# MCU.net
KiCad netlist of a schematic drawn in Altium Designer
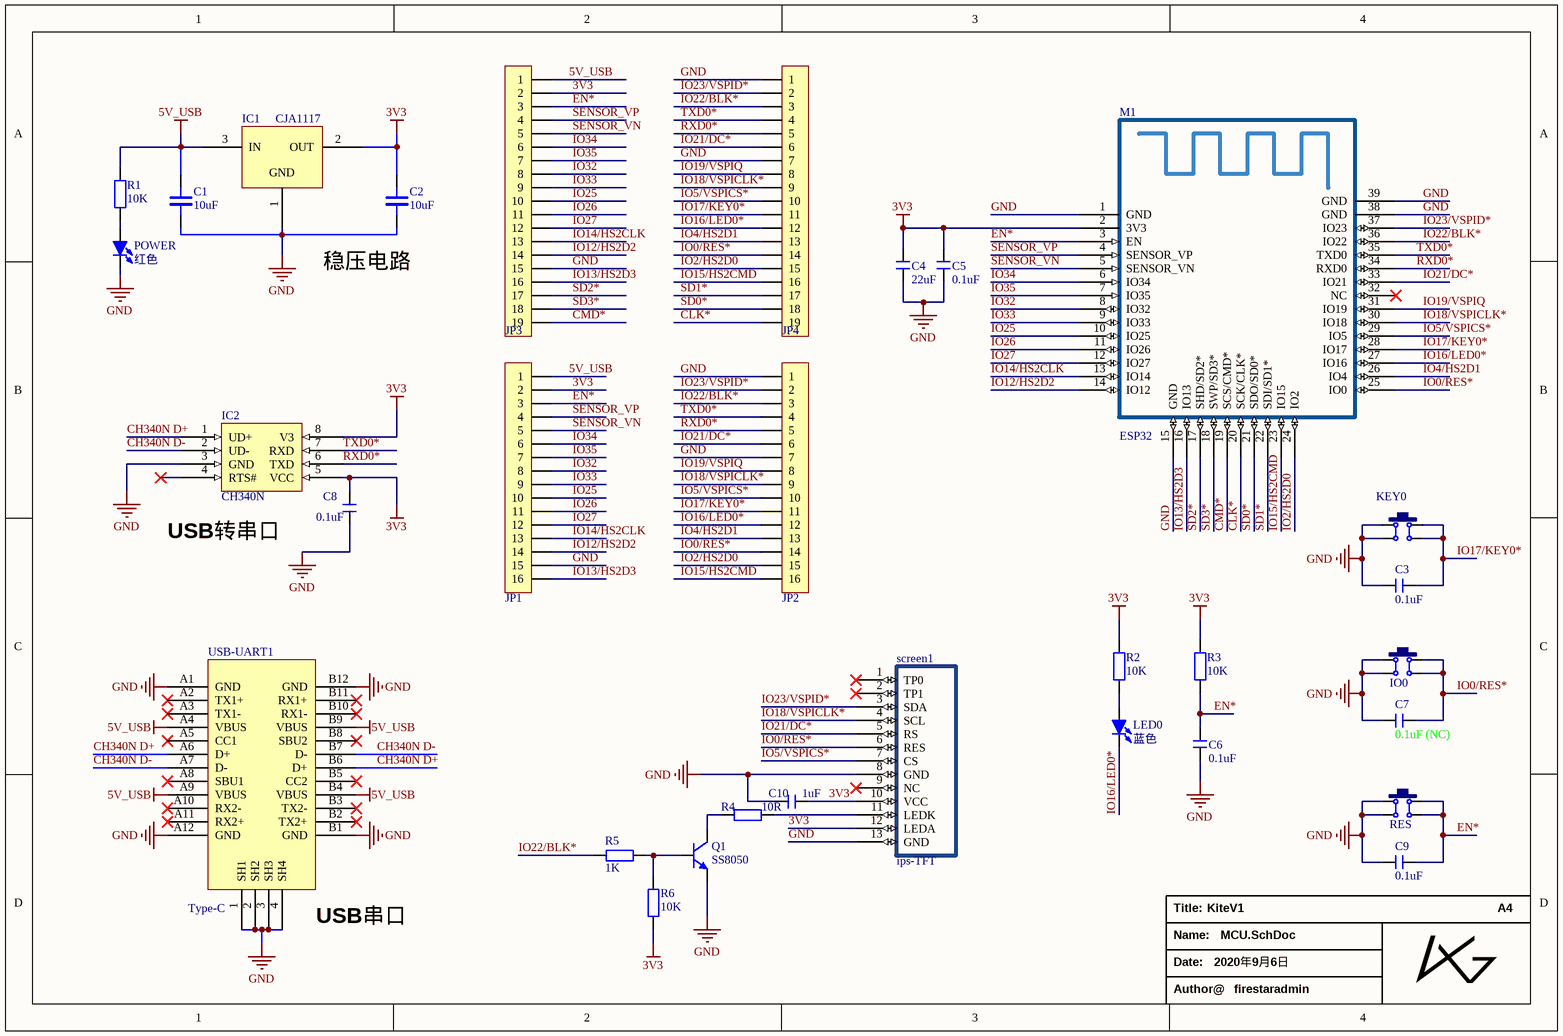
[diagram p0: MCU.SchDoc]

(export (version "E")
  (design (tool "Eeschema 10.0.6"))
  (components
    (comp (ref "C1")
      (value "10uF")
      (footprint "C 0805_L")
      (description "Capacitor")
      (libsource (lib "General") (part "CAP"))
    )
    (comp (ref "C2")
      (value "10uF")
      (footprint "C 0805_L")
      (description "Capacitor")
      (libsource (lib "General") (part "CAP"))
    )
    (comp (ref "C3")
      (value "0.1uF")
      (footprint "C 0603_M")
      (description "无极性贴片电容")
      (fields (field (name "版权归属") "源创客"))
      (libsource (lib "SCH-电阻-电容-电感") (part "C"))
    )
    (comp (ref "C4")
      (value "22uF")
      (footprint "C 0603_M")
      (description "无极性贴片电容")
      (fields (field (name "版权归属") "源创客"))
      (libsource (lib "SCH-电阻-电容-电感") (part "C"))
    )
    (comp (ref "C5")
      (value "0.1uF")
      (footprint "C 0603_M")
      (description "无极性贴片电容")
      (fields (field (name "版权归属") "源创客"))
      (libsource (lib "SCH-电阻-电容-电感") (part "C"))
    )
    (comp (ref "C6")
      (value "0.1uF")
      (footprint "C 0603_M")
      (description "无极性贴片电容")
      (fields (field (name "版权归属") "源创客"))
      (libsource (lib "SCH-电阻-电容-电感") (part "C"))
    )
    (comp (ref "C7")
      (value "0.1uF (NC)")
      (footprint "C 0603_M")
      (description "无极性贴片电容")
      (fields (field (name "版权归属") "源创客"))
      (libsource (lib "SCH-电阻-电容-电感") (part "C"))
    )
    (comp (ref "C8")
      (value "0.1uF")
      (footprint "C 0603_M")
      (description "无极性贴片电容")
      (fields (field (name "版权归属") "源创客"))
      (libsource (lib "altium-import") (part "root_1_C_"))
    )
    (comp (ref "C9")
      (value "0.1uF")
      (footprint "C 0603_M")
      (description "无极性贴片电容")
      (fields (field (name "版权归属") "源创客"))
      (libsource (lib "SCH-电阻-电容-电感") (part "C"))
    )
    (comp (ref "C10")
      (value "1uF")
      (footprint "C 0603_M")
      (description "无极性贴片电容")
      (fields (field (name "版权归属") "源创客"))
      (libsource (lib "SCH-电阻-电容-电感") (part "C"))
    )
    (comp (ref "IC1")
      (value "CJA1117")
      (footprint "SOT89_M")
      (libsource (lib "altium-import") (part "root_0_CJA1117_"))
    )
    (comp (ref "IC2")
      (value "CH340N")
      (footprint "SOP8_M")
      (description "USB 转串口芯片 CH330/CH340N")
      (libsource (lib "altium-import") (part "root_0_CH340N_"))
    )
    (comp (ref "IO0")
      (value "key")
      (footprint "TSMD-3*4*2.5")
      (description "TS-3x4x2.5mm-4pin 轻触按键")
      (libsource (lib "SCH-按键-开关") (part "TS-3x4x2.5mm-4pin"))
    )
    (comp (ref "JP1")
      (value "HDR-1X16")
      (footprint "HDR2.54-LI-16P")
      (description "16P接插件")
      (fields (field (name "版权归属") "源创客"))
      (libsource (lib "SCH-接插件-脚距2.54") (part "Header 16"))
    )
    (comp (ref "JP2")
      (value "HDR-1X16")
      (footprint "HDR2.54-LI-16P")
      (description "16P接插件")
      (fields (field (name "版权归属") "源创客"))
      (libsource (lib "") (part "Header 16_1"))
    )
    (comp (ref "JP3")
      (value "HDR-1X19")
      (footprint "HDR2.54-LI-19P")
      (description "19P接插件")
      (fields (field (name "版权归属") "源创客"))
      (libsource (lib "") (part "Header 19_1"))
    )
    (comp (ref "JP4")
      (value "HDR-1X19")
      (footprint "HDR2.54-LI-19P")
      (description "19P接插件")
      (fields (field (name "版权归属") "源创客"))
      (libsource (lib "SCH-接插件-脚距2.54") (part "Header 19"))
    )
    (comp (ref "KEY0")
      (value "key")
      (footprint "TSMD-3*4*2.5")
      (description "TS-3x4x2.5mm-4pin 轻触按键")
      (libsource (lib "SCH-按键-开关") (part "TS-3x4x2.5mm-4pin"))
    )
    (comp (ref "LED0")
      (value "蓝色")
      (footprint "LED 0603R")
      (description "贴片LED")
      (fields (field (name "版权归属") "源创客"))
      (libsource (lib "SCH-LED") (part "LED-SMD"))
    )
    (comp (ref "M1")
      (value "ESP32")
      (footprint "ESP32-WROOM-32")
      (description "ESP32-WROOM-32 WIFI 蓝牙模组")
      (libsource (lib "SCH- 模块") (part "ESP32-WROOM-32"))
    )
    (comp (ref "POWER")
      (value "红色")
      (footprint "LED 0603R")
      (description "贴片LED")
      (fields (field (name "版权归属") "源创客"))
      (libsource (lib "SCH-LED") (part "LED-SMD"))
    )
    (comp (ref "Q1")
      (value "SS8050")
      (footprint "SOT23-3N")
      (description "高频放大-NPN型")
      (fields (field (name "版权归属") "源创客"))
      (libsource (lib "SCH-三极管") (part "8050-SMD"))
    )
    (comp (ref "R1")
      (value "10K")
      (footprint "R 0603_M")
      (description "贴片电阻")
      (fields (field (name "版权归属") "源创客"))
      (libsource (lib "SCH-电阻-电容-电感") (part "R"))
    )
    (comp (ref "R2")
      (value "10K")
      (footprint "R 0603_M")
      (description "贴片电阻")
      (fields (field (name "版权归属") "源创客"))
      (libsource (lib "SCH-电阻-电容-电感") (part "R"))
    )
    (comp (ref "R3")
      (value "10K")
      (footprint "R 0603_M")
      (description "贴片电阻")
      (fields (field (name "版权归属") "源创客"))
      (libsource (lib "SCH-电阻-电容-电感") (part "R"))
    )
    (comp (ref "R4")
      (value "10R")
      (footprint "R 0603_M")
      (description "贴片电阻")
      (fields (field (name "版权归属") "源创客"))
      (libsource (lib "SCH-电阻-电容-电感") (part "R"))
    )
    (comp (ref "R5")
      (value "1K")
      (footprint "R 0603_M")
      (description "贴片电阻")
      (fields (field (name "版权归属") "源创客"))
      (libsource (lib "SCH-电阻-电容-电感") (part "R"))
    )
    (comp (ref "R6")
      (value "10K")
      (footprint "R 0603_M")
      (description "贴片电阻")
      (fields (field (name "版权归属") "源创客"))
      (libsource (lib "SCH-电阻-电容-电感") (part "R"))
    )
    (comp (ref "RES")
      (value "key")
      (footprint "TSMD-3*4*2.5")
      (description "TS-3x4x2.5mm-4pin 轻触按键")
      (libsource (lib "SCH-按键-开关") (part "TS-3x4x2.5mm-4pin"))
    )
    (comp (ref "screen1")
      (value "ips-TFT")
      (footprint "ips-TFT-0.96寸-st7735-SPI")
      (description "中景园ips 0.96寸TFT显示屏ips液晶屏0.96寸st7735 ips显示屏 13pins")
      (libsource (lib "SCH-显示器件") (part "ips-TFT-0.96寸-st7735-SPI"))
    )
    (comp (ref "USB-UART1")
      (value "Type-C")
      (footprint "Type-C")
      (libsource (lib "altium-import") (part "root_0_Type-C_"))
    )
  )
  (nets
    (net (code "1") (name "/CH340N D+") (class "Default")
      (node (ref "IC2") (pin "1") (pinfunction "UD+_1") (pintype "input"))
      (node (ref "USB-UART1") (pin "A6") (pinfunction "D+_A6") (pintype "passive"))
      (node (ref "USB-UART1") (pin "B6") (pinfunction "D+_B6") (pintype "passive"))
    )
    (net (code "2") (name "/CH340N D-") (class "Default")
      (node (ref "IC2") (pin "2") (pinfunction "UD-_2") (pintype "input"))
      (node (ref "USB-UART1") (pin "A7") (pinfunction "D-_A7") (pintype "passive"))
      (node (ref "USB-UART1") (pin "B7") (pinfunction "D-_B7") (pintype "passive"))
    )
    (net (code "3") (name "/CLK*") (class "Default")
      (node (ref "JP4") (pin "19") (pinfunction "19_19") (pintype "passive"))
      (node (ref "M1") (pin "20") (pinfunction "SCK/CLK*_20") (pintype "bidirectional"))
    )
    (net (code "4") (name "/CMD*") (class "Default")
      (node (ref "JP3") (pin "19") (pinfunction "19_19") (pintype "passive"))
      (node (ref "M1") (pin "19") (pinfunction "SCS/CMD*_19") (pintype "bidirectional"))
    )
    (net (code "5") (name "/EN*") (class "Default")
      (node (ref "C6") (pin "1") (pinfunction "1_1") (pintype "passive"))
      (node (ref "C9") (pin "2") (pinfunction "2_2") (pintype "passive"))
      (node (ref "JP1") (pin "3") (pinfunction "3_3") (pintype "passive"))
      (node (ref "JP3") (pin "3") (pinfunction "3_3") (pintype "passive"))
      (node (ref "M1") (pin "3") (pinfunction "EN_3") (pintype "input"))
      (node (ref "R3") (pin "1") (pinfunction "1_1") (pintype "passive"))
      (node (ref "RES") (pin "3") (pinfunction "3_3") (pintype "passive"))
      (node (ref "RES") (pin "4") (pinfunction "4_4") (pintype "passive"))
    )
    (net (code "6") (name "/IO0{slash}RES*") (class "Default")
      (node (ref "C7") (pin "2") (pinfunction "2_2") (pintype "passive"))
      (node (ref "IO0") (pin "3") (pinfunction "3_3") (pintype "passive"))
      (node (ref "IO0") (pin "4") (pinfunction "4_4") (pintype "passive"))
      (node (ref "JP2") (pin "14") (pinfunction "14_14") (pintype "passive"))
      (node (ref "JP4") (pin "14") (pinfunction "14_14") (pintype "passive"))
      (node (ref "M1") (pin "25") (pinfunction "IO0_25") (pintype "bidirectional"))
      (node (ref "screen1") (pin "6") (pinfunction "RES_6") (pintype "bidirectional"))
    )
    (net (code "7") (name "/IO2{slash}HS2D0") (class "Default")
      (node (ref "JP2") (pin "15") (pinfunction "15_15") (pintype "passive"))
      (node (ref "JP4") (pin "15") (pinfunction "15_15") (pintype "passive"))
      (node (ref "M1") (pin "24") (pinfunction "IO2_24") (pintype "bidirectional"))
    )
    (net (code "8") (name "/IO4{slash}HS2D1") (class "Default")
      (node (ref "JP2") (pin "13") (pinfunction "13_13") (pintype "passive"))
      (node (ref "JP4") (pin "13") (pinfunction "13_13") (pintype "passive"))
      (node (ref "M1") (pin "26") (pinfunction "IO4_26") (pintype "bidirectional"))
    )
    (net (code "9") (name "/IO5{slash}VSPICS*") (class "Default")
      (node (ref "JP2") (pin "10") (pinfunction "10_10") (pintype "passive"))
      (node (ref "JP4") (pin "10") (pinfunction "10_10") (pintype "passive"))
      (node (ref "M1") (pin "29") (pinfunction "IO5_29") (pintype "bidirectional"))
      (node (ref "screen1") (pin "7") (pinfunction "CS_7") (pintype "bidirectional"))
    )
    (net (code "10") (name "/IO12{slash}HS2D2") (class "Default")
      (node (ref "JP1") (pin "14") (pinfunction "14_14") (pintype "passive"))
      (node (ref "JP3") (pin "14") (pinfunction "14_14") (pintype "passive"))
      (node (ref "M1") (pin "14") (pinfunction "IO12_14") (pintype "bidirectional"))
    )
    (net (code "11") (name "/IO13{slash}HS2D3") (class "Default")
      (node (ref "JP1") (pin "16") (pinfunction "16_16") (pintype "passive"))
      (node (ref "JP3") (pin "16") (pinfunction "16_16") (pintype "passive"))
      (node (ref "M1") (pin "16") (pinfunction "IO13_16") (pintype "bidirectional"))
    )
    (net (code "12") (name "/IO14{slash}HS2CLK") (class "Default")
      (node (ref "JP1") (pin "13") (pinfunction "13_13") (pintype "passive"))
      (node (ref "JP3") (pin "13") (pinfunction "13_13") (pintype "passive"))
      (node (ref "M1") (pin "13") (pinfunction "IO14_13") (pintype "bidirectional"))
    )
    (net (code "13") (name "/IO15{slash}HS2CMD") (class "Default")
      (node (ref "JP2") (pin "16") (pinfunction "16_16") (pintype "passive"))
      (node (ref "JP4") (pin "16") (pinfunction "16_16") (pintype "passive"))
      (node (ref "M1") (pin "23") (pinfunction "IO15_23") (pintype "bidirectional"))
    )
    (net (code "14") (name "/IO16{slash}LED0*") (class "Default")
      (node (ref "JP2") (pin "12") (pinfunction "12_12") (pintype "passive"))
      (node (ref "JP4") (pin "12") (pinfunction "12_12") (pintype "passive"))
      (node (ref "LED0") (pin "2") (pinfunction "K_2") (pintype "passive"))
      (node (ref "M1") (pin "27") (pinfunction "IO16_27") (pintype "bidirectional"))
    )
    (net (code "15") (name "/IO17{slash}KEY0*") (class "Default")
      (node (ref "C3") (pin "2") (pinfunction "2_2") (pintype "passive"))
      (node (ref "JP2") (pin "11") (pinfunction "11_11") (pintype "passive"))
      (node (ref "JP4") (pin "11") (pinfunction "11_11") (pintype "passive"))
      (node (ref "KEY0") (pin "3") (pinfunction "3_3") (pintype "passive"))
      (node (ref "KEY0") (pin "4") (pinfunction "4_4") (pintype "passive"))
      (node (ref "M1") (pin "28") (pinfunction "IO17_28") (pintype "bidirectional"))
    )
    (net (code "16") (name "/IO18{slash}VSPICLK*") (class "Default")
      (node (ref "JP2") (pin "9") (pinfunction "9_9") (pintype "passive"))
      (node (ref "JP4") (pin "9") (pinfunction "9_9") (pintype "passive"))
      (node (ref "M1") (pin "30") (pinfunction "IO18_30") (pintype "bidirectional"))
      (node (ref "screen1") (pin "4") (pinfunction "SCL_4") (pintype "bidirectional"))
    )
    (net (code "17") (name "/IO19{slash}VSPIQ") (class "Default")
      (node (ref "JP2") (pin "8") (pinfunction "8_8") (pintype "passive"))
      (node (ref "JP4") (pin "8") (pinfunction "8_8") (pintype "passive"))
      (node (ref "M1") (pin "31") (pinfunction "IO19_31") (pintype "bidirectional"))
    )
    (net (code "18") (name "/IO21{slash}DC*") (class "Default")
      (node (ref "JP2") (pin "6") (pinfunction "6_6") (pintype "passive"))
      (node (ref "JP4") (pin "6") (pinfunction "6_6") (pintype "passive"))
      (node (ref "M1") (pin "33") (pinfunction "IO21_33") (pintype "bidirectional"))
      (node (ref "screen1") (pin "5") (pinfunction "RS_5") (pintype "bidirectional"))
    )
    (net (code "19") (name "/IO22{slash}BLK*") (class "Default")
      (node (ref "JP2") (pin "3") (pinfunction "3_3") (pintype "passive"))
      (node (ref "JP4") (pin "3") (pinfunction "3_3") (pintype "passive"))
      (node (ref "M1") (pin "36") (pinfunction "IO22_36") (pintype "bidirectional"))
      (node (ref "R5") (pin "2") (pinfunction "2_2") (pintype "passive"))
    )
    (net (code "20") (name "/IO23{slash}VSPID*") (class "Default")
      (node (ref "JP2") (pin "2") (pinfunction "2_2") (pintype "passive"))
      (node (ref "JP4") (pin "2") (pinfunction "2_2") (pintype "passive"))
      (node (ref "M1") (pin "37") (pinfunction "IO23_37") (pintype "bidirectional"))
      (node (ref "screen1") (pin "3") (pinfunction "SDA_3") (pintype "bidirectional"))
    )
    (net (code "21") (name "/IO25") (class "Default")
      (node (ref "JP1") (pin "10") (pinfunction "10_10") (pintype "passive"))
      (node (ref "JP3") (pin "10") (pinfunction "10_10") (pintype "passive"))
      (node (ref "M1") (pin "10") (pinfunction "IO25_10") (pintype "bidirectional"))
    )
    (net (code "22") (name "/IO26") (class "Default")
      (node (ref "JP1") (pin "11") (pinfunction "11_11") (pintype "passive"))
      (node (ref "JP3") (pin "11") (pinfunction "11_11") (pintype "passive"))
      (node (ref "M1") (pin "11") (pinfunction "IO26_11") (pintype "bidirectional"))
    )
    (net (code "23") (name "/IO27") (class "Default")
      (node (ref "JP1") (pin "12") (pinfunction "12_12") (pintype "passive"))
      (node (ref "JP3") (pin "12") (pinfunction "12_12") (pintype "passive"))
      (node (ref "M1") (pin "12") (pinfunction "IO27_12") (pintype "bidirectional"))
    )
    (net (code "24") (name "/IO32") (class "Default")
      (node (ref "JP1") (pin "8") (pinfunction "8_8") (pintype "passive"))
      (node (ref "JP3") (pin "8") (pinfunction "8_8") (pintype "passive"))
      (node (ref "M1") (pin "8") (pinfunction "IO32_8") (pintype "bidirectional"))
    )
    (net (code "25") (name "/IO33") (class "Default")
      (node (ref "JP1") (pin "9") (pinfunction "9_9") (pintype "passive"))
      (node (ref "JP3") (pin "9") (pinfunction "9_9") (pintype "passive"))
      (node (ref "M1") (pin "9") (pinfunction "IO33_9") (pintype "bidirectional"))
    )
    (net (code "26") (name "/IO34") (class "Default")
      (node (ref "JP1") (pin "6") (pinfunction "6_6") (pintype "passive"))
      (node (ref "JP3") (pin "6") (pinfunction "6_6") (pintype "passive"))
      (node (ref "M1") (pin "6") (pinfunction "IO34_6") (pintype "input"))
    )
    (net (code "27") (name "/IO35") (class "Default")
      (node (ref "JP1") (pin "7") (pinfunction "7_7") (pintype "passive"))
      (node (ref "JP3") (pin "7") (pinfunction "7_7") (pintype "passive"))
      (node (ref "M1") (pin "7") (pinfunction "IO35_7") (pintype "input"))
    )
    (net (code "28") (name "/RXD0*") (class "Default")
      (node (ref "IC2") (pin "6") (pinfunction "TXD_6") (pintype "input"))
      (node (ref "JP2") (pin "5") (pinfunction "5_5") (pintype "passive"))
      (node (ref "JP4") (pin "5") (pinfunction "5_5") (pintype "passive"))
      (node (ref "M1") (pin "34") (pinfunction "RXD0_34") (pintype "bidirectional"))
    )
    (net (code "29") (name "/SD0*") (class "Default")
      (node (ref "JP4") (pin "18") (pinfunction "18_18") (pintype "passive"))
      (node (ref "M1") (pin "21") (pinfunction "SDO/SD0*_21") (pintype "bidirectional"))
    )
    (net (code "30") (name "/SD1*") (class "Default")
      (node (ref "JP4") (pin "17") (pinfunction "17_17") (pintype "passive"))
      (node (ref "M1") (pin "22") (pinfunction "SDI/SD1*_22") (pintype "bidirectional"))
    )
    (net (code "31") (name "/SD2*") (class "Default")
      (node (ref "JP3") (pin "17") (pinfunction "17_17") (pintype "passive"))
      (node (ref "M1") (pin "17") (pinfunction "SHD/SD2*_17") (pintype "bidirectional"))
    )
    (net (code "32") (name "/SD3*") (class "Default")
      (node (ref "JP3") (pin "18") (pinfunction "18_18") (pintype "passive"))
      (node (ref "M1") (pin "18") (pinfunction "SWP/SD3*_18") (pintype "bidirectional"))
    )
    (net (code "33") (name "/SENSOR_VN") (class "Default")
      (node (ref "JP1") (pin "5") (pinfunction "5_5") (pintype "passive"))
      (node (ref "JP3") (pin "5") (pinfunction "5_5") (pintype "passive"))
      (node (ref "M1") (pin "5") (pinfunction "SENSOR_VN_5") (pintype "input"))
    )
    (net (code "34") (name "/SENSOR_VP") (class "Default")
      (node (ref "JP1") (pin "4") (pinfunction "4_4") (pintype "passive"))
      (node (ref "JP3") (pin "4") (pinfunction "4_4") (pintype "passive"))
      (node (ref "M1") (pin "4") (pinfunction "SENSOR_VP_4") (pintype "input"))
    )
    (net (code "35") (name "/TXD0*") (class "Default")
      (node (ref "IC2") (pin "7") (pinfunction "RXD_7") (pintype "input"))
      (node (ref "JP2") (pin "4") (pinfunction "4_4") (pintype "passive"))
      (node (ref "JP4") (pin "4") (pinfunction "4_4") (pintype "passive"))
      (node (ref "M1") (pin "35") (pinfunction "TXD0_35") (pintype "bidirectional"))
    )
    (net (code "36") (name "3V3") (class "Default")
      (node (ref "C10") (pin "2") (pinfunction "2_2") (pintype "passive"))
      (node (ref "C2") (pin "1") (pinfunction "1_1") (pintype "passive"))
      (node (ref "C4") (pin "1") (pinfunction "1_1") (pintype "passive"))
      (node (ref "C5") (pin "1") (pinfunction "1_1") (pintype "passive"))
      (node (ref "C8") (pin "2") (pinfunction "2_2") (pintype "passive"))
      (node (ref "IC1") (pin "2") (pinfunction "OUT_2") (pintype "passive"))
      (node (ref "IC2") (pin "5") (pinfunction "VCC_5") (pintype "input"))
      (node (ref "IC2") (pin "8") (pinfunction "V3_8") (pintype "input"))
      (node (ref "JP1") (pin "2") (pinfunction "2_2") (pintype "passive"))
      (node (ref "JP3") (pin "2") (pinfunction "2_2") (pintype "passive"))
      (node (ref "M1") (pin "2") (pinfunction "3V3_2") (pintype "power_in"))
      (node (ref "R2") (pin "2") (pinfunction "2_2") (pintype "passive"))
      (node (ref "R3") (pin "2") (pinfunction "2_2") (pintype "passive"))
      (node (ref "R6") (pin "1") (pinfunction "1_1") (pintype "passive"))
      (node (ref "screen1") (pin "10") (pinfunction "VCC_10") (pintype "bidirectional"))
      (node (ref "screen1") (pin "12") (pinfunction "LEDA_12") (pintype "bidirectional"))
    )
    (net (code "37") (name "5V_USB") (class "Default")
      (node (ref "C1") (pin "1") (pinfunction "1_1") (pintype "passive"))
      (node (ref "IC1") (pin "3") (pinfunction "IN_3") (pintype "passive"))
      (node (ref "JP1") (pin "1") (pinfunction "1_1") (pintype "passive"))
      (node (ref "JP3") (pin "1") (pinfunction "1_1") (pintype "passive"))
      (node (ref "R1") (pin "2") (pinfunction "2_2") (pintype "passive"))
      (node (ref "USB-UART1") (pin "A4") (pinfunction "VBUS_A4") (pintype "passive"))
      (node (ref "USB-UART1") (pin "A9") (pinfunction "VBUS_A9") (pintype "passive"))
      (node (ref "USB-UART1") (pin "B4") (pinfunction "VBUS_B4") (pintype "passive"))
      (node (ref "USB-UART1") (pin "B9") (pinfunction "VBUS_B9") (pintype "passive"))
    )
    (net (code "38") (name "GND") (class "Default")
      (node (ref "C1") (pin "2") (pinfunction "2_2") (pintype "passive"))
      (node (ref "C10") (pin "1") (pinfunction "1_1") (pintype "passive"))
      (node (ref "C2") (pin "2") (pinfunction "2_2") (pintype "passive"))
      (node (ref "C3") (pin "1") (pinfunction "1_1") (pintype "passive"))
      (node (ref "C4") (pin "2") (pinfunction "2_2") (pintype "passive"))
      (node (ref "C5") (pin "2") (pinfunction "2_2") (pintype "passive"))
      (node (ref "C6") (pin "2") (pinfunction "2_2") (pintype "passive"))
      (node (ref "C7") (pin "1") (pinfunction "1_1") (pintype "passive"))
      (node (ref "C8") (pin "1") (pinfunction "1_1") (pintype "passive"))
      (node (ref "C9") (pin "1") (pinfunction "1_1") (pintype "passive"))
      (node (ref "IC1") (pin "1") (pinfunction "GND_1") (pintype "passive"))
      (node (ref "IC2") (pin "3") (pinfunction "GND_3") (pintype "input"))
      (node (ref "IO0") (pin "1") (pinfunction "1_1") (pintype "passive"))
      (node (ref "IO0") (pin "2") (pinfunction "2_2") (pintype "passive"))
      (node (ref "JP1") (pin "15") (pinfunction "15_15") (pintype "passive"))
      (node (ref "JP2") (pin "1") (pinfunction "1_1") (pintype "passive"))
      (node (ref "JP2") (pin "7") (pinfunction "7_7") (pintype "passive"))
      (node (ref "JP3") (pin "15") (pinfunction "15_15") (pintype "passive"))
      (node (ref "JP4") (pin "1") (pinfunction "1_1") (pintype "passive"))
      (node (ref "JP4") (pin "7") (pinfunction "7_7") (pintype "passive"))
      (node (ref "KEY0") (pin "1") (pinfunction "1_1") (pintype "passive"))
      (node (ref "KEY0") (pin "2") (pinfunction "2_2") (pintype "passive"))
      (node (ref "M1") (pin "1") (pinfunction "GND_1") (pintype "power_in"))
      (node (ref "M1") (pin "15") (pinfunction "GND_15") (pintype "bidirectional"))
      (node (ref "M1") (pin "38") (pinfunction "GND_38") (pintype "power_in"))
      (node (ref "M1") (pin "39") (pinfunction "GND_39") (pintype "power_in"))
      (node (ref "POWER") (pin "2") (pinfunction "K_2") (pintype "passive"))
      (node (ref "Q1") (pin "2") (pinfunction "E_2") (pintype "passive"))
      (node (ref "RES") (pin "1") (pinfunction "1_1") (pintype "passive"))
      (node (ref "RES") (pin "2") (pinfunction "2_2") (pintype "passive"))
      (node (ref "USB-UART1") (pin "1") (pinfunction "SH1_1") (pintype "passive"))
      (node (ref "USB-UART1") (pin "2") (pinfunction "SH2_2") (pintype "passive"))
      (node (ref "USB-UART1") (pin "3") (pinfunction "SH3_3") (pintype "passive"))
      (node (ref "USB-UART1") (pin "4") (pinfunction "SH4_4") (pintype "passive"))
      (node (ref "USB-UART1") (pin "A1") (pinfunction "GND_A1") (pintype "passive"))
      (node (ref "USB-UART1") (pin "A12") (pinfunction "GND_A12") (pintype "passive"))
      (node (ref "USB-UART1") (pin "B1") (pinfunction "GND_B1") (pintype "passive"))
      (node (ref "USB-UART1") (pin "B12") (pinfunction "GND_B12") (pintype "passive"))
      (node (ref "screen1") (pin "13") (pinfunction "GND_13") (pintype "bidirectional"))
      (node (ref "screen1") (pin "8") (pinfunction "GND_8") (pintype "bidirectional"))
    )
    (net (code "39") (name "Net-(LED0-A)") (class "Default")
      (node (ref "LED0") (pin "1") (pinfunction "A_1") (pintype "passive"))
      (node (ref "R2") (pin "1") (pinfunction "1_1") (pintype "passive"))
    )
    (net (code "40") (name "Net-(POWER-A)") (class "Default")
      (node (ref "POWER") (pin "1") (pinfunction "A_1") (pintype "passive"))
      (node (ref "R1") (pin "1") (pinfunction "1_1") (pintype "passive"))
    )
    (net (code "41") (name "Net-(Q1-B)") (class "Default")
      (node (ref "Q1") (pin "1") (pinfunction "B_1") (pintype "passive"))
      (node (ref "R5") (pin "1") (pinfunction "1_1") (pintype "passive"))
      (node (ref "R6") (pin "2") (pinfunction "2_2") (pintype "passive"))
    )
    (net (code "42") (name "Net-(Q1-C)") (class "Default")
      (node (ref "Q1") (pin "3") (pinfunction "C_3") (pintype "passive"))
      (node (ref "R4") (pin "2") (pinfunction "2_2") (pintype "passive"))
    )
    (net (code "43") (name "Net-(screen1-LEDK)") (class "Default")
      (node (ref "R4") (pin "1") (pinfunction "1_1") (pintype "passive"))
      (node (ref "screen1") (pin "11") (pinfunction "LEDK_11") (pintype "bidirectional"))
    )
    (net (code "44") (name "unconnected-(IC2-RTS#-Pad4)") (class "Default")
      (node (ref "IC2") (pin "4") (pinfunction "RTS#_4") (pintype "input+no_connect"))
    )
    (net (code "45") (name "unconnected-(M1-NC-Pad32)") (class "Default")
      (node (ref "M1") (pin "32") (pinfunction "NC_32") (pintype "bidirectional+no_connect"))
    )
    (net (code "46") (name "unconnected-(USB-UART1-CC1-PadA5)") (class "Default")
      (node (ref "USB-UART1") (pin "A5") (pinfunction "CC1_A5") (pintype "passive+no_connect"))
    )
    (net (code "47") (name "unconnected-(USB-UART1-CC2-PadB5)") (class "Default")
      (node (ref "USB-UART1") (pin "B5") (pinfunction "CC2_B5") (pintype "passive+no_connect"))
    )
    (net (code "48") (name "unconnected-(USB-UART1-RX1+-PadB11)") (class "Default")
      (node (ref "USB-UART1") (pin "B11") (pinfunction "RX1+_B11") (pintype "passive+no_connect"))
    )
    (net (code "49") (name "unconnected-(USB-UART1-RX1--PadB10)") (class "Default")
      (node (ref "USB-UART1") (pin "B10") (pinfunction "RX1-_B10") (pintype "passive+no_connect"))
    )
    (net (code "50") (name "unconnected-(USB-UART1-RX2+-PadA11)") (class "Default")
      (node (ref "USB-UART1") (pin "A11") (pinfunction "RX2+_A11") (pintype "passive+no_connect"))
    )
    (net (code "51") (name "unconnected-(USB-UART1-RX2--PadA10)") (class "Default")
      (node (ref "USB-UART1") (pin "A10") (pinfunction "RX2-_A10") (pintype "passive+no_connect"))
    )
    (net (code "52") (name "unconnected-(USB-UART1-SBU1-PadA8)") (class "Default")
      (node (ref "USB-UART1") (pin "A8") (pinfunction "SBU1_A8") (pintype "passive+no_connect"))
    )
    (net (code "53") (name "unconnected-(USB-UART1-SBU2-PadB8)") (class "Default")
      (node (ref "USB-UART1") (pin "B8") (pinfunction "SBU2_B8") (pintype "passive+no_connect"))
    )
    (net (code "54") (name "unconnected-(USB-UART1-TX1+-PadA2)") (class "Default")
      (node (ref "USB-UART1") (pin "A2") (pinfunction "TX1+_A2") (pintype "passive+no_connect"))
    )
    (net (code "55") (name "unconnected-(USB-UART1-TX1--PadA3)") (class "Default")
      (node (ref "USB-UART1") (pin "A3") (pinfunction "TX1-_A3") (pintype "passive+no_connect"))
    )
    (net (code "56") (name "unconnected-(USB-UART1-TX2+-PadB2)") (class "Default")
      (node (ref "USB-UART1") (pin "B2") (pinfunction "TX2+_B2") (pintype "passive+no_connect"))
    )
    (net (code "57") (name "unconnected-(USB-UART1-TX2--PadB3)") (class "Default")
      (node (ref "USB-UART1") (pin "B3") (pinfunction "TX2-_B3") (pintype "passive+no_connect"))
    )
    (net (code "58") (name "unconnected-(screen1-NC-Pad9)") (class "Default")
      (node (ref "screen1") (pin "9") (pinfunction "NC_9") (pintype "bidirectional+no_connect"))
    )
    (net (code "59") (name "unconnected-(screen1-TP0-Pad1)") (class "Default")
      (node (ref "screen1") (pin "1") (pinfunction "TP0_1") (pintype "bidirectional+no_connect"))
    )
    (net (code "60") (name "unconnected-(screen1-TP1-Pad2)") (class "Default")
      (node (ref "screen1") (pin "2") (pinfunction "TP1_2") (pintype "bidirectional+no_connect"))
    )
  )
)
